# vcf-lm324-mono.net
KiCad netlist of a schematic drawn in EAGLE
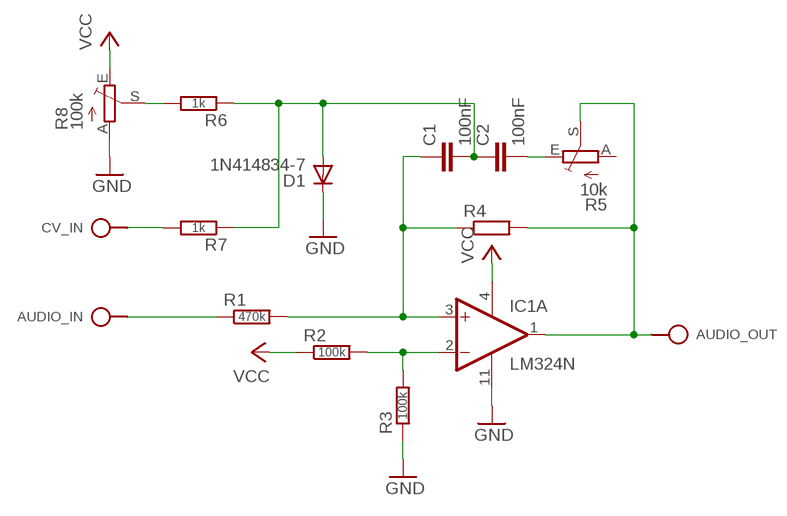
[diagram p0: schematic, sheet 1]

(export (version "E")
  (design (tool "Eeschema 10.0.6"))
  (components
    (comp (ref "AUDIO_IN")
      (value "SPAD")
      (footprint "eagle-import:SPAD")
      (libsource (lib "eagle-import") (part "SPAD"))
    )
    (comp (ref "AUDIO_OUT")
      (value "SPAD")
      (footprint "eagle-import:SPAD")
      (libsource (lib "eagle-import") (part "SPAD"))
    )
    (comp (ref "C1")
      (value "100nF")
      (footprint "eagle-import:C050-024X044")
      (libsource (lib "eagle-import") (part "C050-024X044"))
    )
    (comp (ref "C2")
      (value "100nF")
      (footprint "eagle-import:C050-024X044")
      (libsource (lib "eagle-import") (part "C050-024X044"))
    )
    (comp (ref "CV_IN")
      (value "SPAD")
      (footprint "eagle-import:SPAD")
      (libsource (lib "eagle-import") (part "SPAD"))
    )
    (comp (ref "D1")
      (value "1N414834-7")
      (footprint "eagle-import:DO34-7")
      (libsource (lib "eagle-import") (part "1N414834-7"))
    )
    (comp (ref "IC1")
      (value "LM324N")
      (footprint "eagle-import:DIL14")
      (libsource (lib "eagle-import") (part "LM324N"))
    )
    (comp (ref "R1")
      (value "470k")
      (footprint "eagle-import:0202_7")
      (libsource (lib "eagle-import") (part "R0202/7"))
    )
    (comp (ref "R2")
      (value "100k")
      (footprint "eagle-import:0202_7")
      (libsource (lib "eagle-import") (part "R0202/7"))
    )
    (comp (ref "R3")
      (value "100k")
      (footprint "eagle-import:0202_7")
      (libsource (lib "eagle-import") (part "R0202/7"))
    )
    (comp (ref "R4")
      (value "R0202/7")
      (footprint "eagle-import:0202_7")
      (libsource (lib "eagle-import") (part "R0202/7"))
    )
    (comp (ref "R5")
      (value "10k")
      (footprint "eagle-import:RJ9W")
      (libsource (lib "eagle-import") (part "TRIM_EU-RJ9W"))
    )
    (comp (ref "R6")
      (value "1k")
      (footprint "eagle-import:0202_7")
      (libsource (lib "eagle-import") (part "R0202/7"))
    )
    (comp (ref "R7")
      (value "1k")
      (footprint "eagle-import:0202_7")
      (libsource (lib "eagle-import") (part "R0202/7"))
    )
    (comp (ref "R8")
      (value "100k")
      (footprint "eagle-import:RJ9W")
      (libsource (lib "eagle-import") (part "TRIM_EU-RJ9W"))
    )
  )
  (nets
    (net (code "1") (name "GND") (class "Default")
      (node (ref "D1") (pin "C") (pinfunction "C_C") (pintype "passive"))
      (node (ref "IC1") (pin "11") (pinfunction "V-_11") (pintype "power_in"))
      (node (ref "R3") (pin "1") (pinfunction "1_1") (pintype "passive"))
      (node (ref "R8") (pin "A") (pinfunction "A_A") (pintype "passive"))
    )
    (net (code "2") (name "Net-(AUDIO_IN-P$1)") (class "Default")
      (node (ref "AUDIO_IN") (pin "1") (pinfunction "P$1_1") (pintype "bidirectional"))
      (node (ref "R1") (pin "1") (pinfunction "1_1") (pintype "passive"))
    )
    (net (code "3") (name "Net-(AUDIO_OUT-P$1)") (class "Default")
      (node (ref "AUDIO_OUT") (pin "1") (pinfunction "P$1_1") (pintype "bidirectional"))
      (node (ref "IC1") (pin "1") (pinfunction "OUT_1") (pintype "output"))
      (node (ref "R4") (pin "2") (pinfunction "2_2") (pintype "passive"))
      (node (ref "R5") (pin "S") (pinfunction "S_S") (pintype "passive"))
    )
    (net (code "4") (name "Net-(C1-Pad2)") (class "Default")
      (node (ref "C1") (pin "2") (pinfunction "2_2") (pintype "passive"))
      (node (ref "C2") (pin "1") (pinfunction "1_1") (pintype "passive"))
      (node (ref "D1") (pin "A") (pinfunction "A_A") (pintype "passive"))
      (node (ref "R6") (pin "1") (pinfunction "1_1") (pintype "passive"))
      (node (ref "R7") (pin "1") (pinfunction "1_1") (pintype "passive"))
    )
    (net (code "5") (name "Net-(C2-Pad2)") (class "Default")
      (node (ref "C2") (pin "2") (pinfunction "2_2") (pintype "passive"))
      (node (ref "R5") (pin "E") (pinfunction "E_E") (pintype "passive"))
    )
    (net (code "6") (name "Net-(CV_IN-P$1)") (class "Default")
      (node (ref "CV_IN") (pin "1") (pinfunction "P$1_1") (pintype "bidirectional"))
      (node (ref "R7") (pin "2") (pinfunction "2_2") (pintype "passive"))
    )
    (net (code "7") (name "Net-(IC1A-+IN)") (class "Default")
      (node (ref "C1") (pin "1") (pinfunction "1_1") (pintype "passive"))
      (node (ref "IC1") (pin "3") (pinfunction "+IN_3") (pintype "input"))
      (node (ref "R1") (pin "2") (pinfunction "2_2") (pintype "passive"))
      (node (ref "R4") (pin "1") (pinfunction "1_1") (pintype "passive"))
    )
    (net (code "8") (name "Net-(IC1A--IN)") (class "Default")
      (node (ref "IC1") (pin "2") (pinfunction "-IN_2") (pintype "input"))
      (node (ref "R2") (pin "2") (pinfunction "2_2") (pintype "passive"))
      (node (ref "R3") (pin "2") (pinfunction "2_2") (pintype "passive"))
    )
    (net (code "9") (name "Net-(R6-Pad2)") (class "Default")
      (node (ref "R6") (pin "2") (pinfunction "2_2") (pintype "passive"))
      (node (ref "R8") (pin "S") (pinfunction "S_S") (pintype "passive"))
    )
    (net (code "10") (name "VCC") (class "Default")
      (node (ref "IC1") (pin "4") (pinfunction "V+_4") (pintype "power_in"))
      (node (ref "R2") (pin "1") (pinfunction "1_1") (pintype "passive"))
      (node (ref "R8") (pin "E") (pinfunction "E_E") (pintype "passive"))
    )
    (net (code "11") (name "unconnected-(R5-PadA)") (class "Default")
      (node (ref "R5") (pin "A") (pinfunction "A_A") (pintype "passive"))
    )
  )
)
